# integrator_inverter.net
KiCad netlist of a schematic drawn in Altium Designer
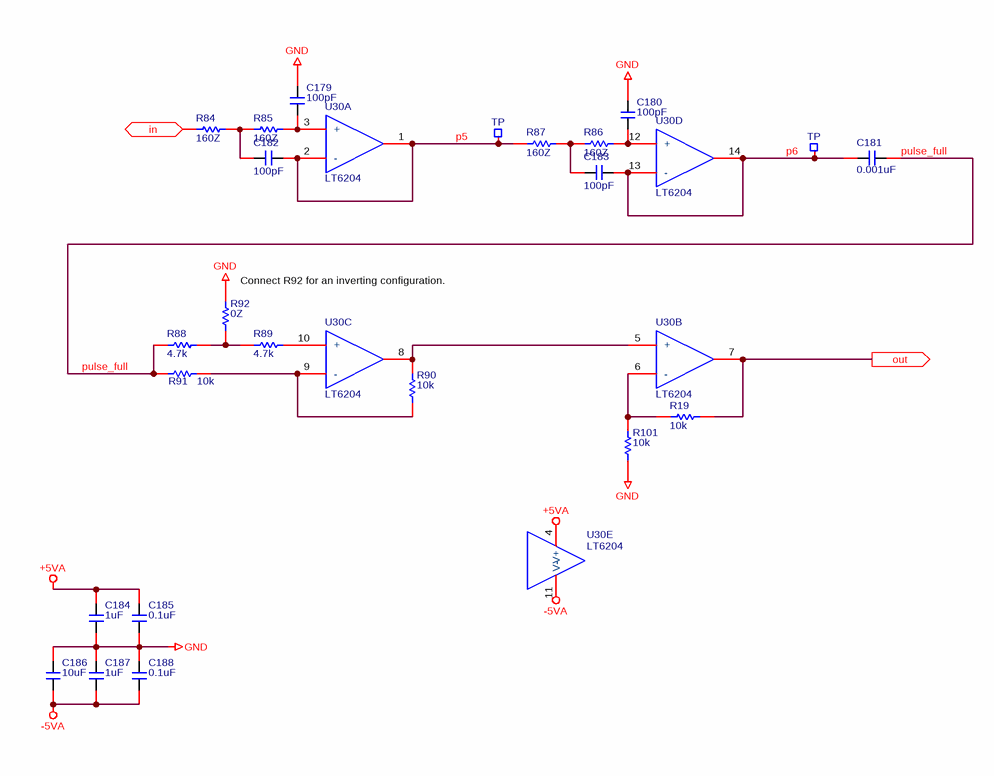
[diagram p0: integrator_inverter.SchDoc]

(export (version "E")
  (design (tool "Eeschema 10.0.6"))
  (components
    (comp (ref "C179")
      (value "100pF")
      (footprint "C0603")
      (description "CAP-CER, 0, 100pF, 10%, 50V, 0603")
      (fields
        (field (name "MANUFACTURER") "AVX Corporation")
        (field (name "MANUFACTURER PART NUMBER") "06035A101KAT2A")
      )
      (libsource (lib "stdlib") (part "AVX/06035A101KAT2A"))
    )
    (comp (ref "C180")
      (value "100pF")
      (footprint "C0603")
      (description "CAP-CER, 0, 100pF, 10%, 50V, 0603")
      (fields
        (field (name "MANUFACTURER") "AVX Corporation")
        (field (name "MANUFACTURER PART NUMBER") "06035A101KAT2A")
      )
      (libsource (lib "stdlib") (part "AVX/06035A101KAT2A"))
    )
    (comp (ref "C181")
      (value "0.001uF")
      (footprint "C0603")
      (description "CAP-CER, 0, 1000pF, 10%, 50V, 0603")
      (fields
        (field (name "MANUFACTURER") "Murata Electronics North America")
        (field (name "MANUFACTURER PART NUMBER") "GRM188R71H102KA01D")
      )
      (libsource (lib "stdlib") (part "CAP/GRM188R71H102KA01D"))
    )
    (comp (ref "C182")
      (value "100pF")
      (footprint "C0603")
      (description "CAP-CER, 0, 100pF, 10%, 50V, 0603")
      (fields
        (field (name "MANUFACTURER") "AVX Corporation")
        (field (name "MANUFACTURER PART NUMBER") "06035A101KAT2A")
      )
      (libsource (lib "stdlib") (part "AVX/06035A101KAT2A"))
    )
    (comp (ref "C183")
      (value "100pF")
      (footprint "C0603")
      (description "CAP-CER, 0, 100pF, 10%, 50V, 0603")
      (fields
        (field (name "MANUFACTURER") "AVX Corporation")
        (field (name "MANUFACTURER PART NUMBER") "06035A101KAT2A")
      )
      (libsource (lib "stdlib") (part "AVX/06035A101KAT2A"))
    )
    (comp (ref "C184")
      (value "1uF")
      (footprint "C0603")
      (description "CAP-CER, 2, 1.0uF, 10%, 25V, 0603")
      (fields
        (field (name "MANUFACTURER") "Murata Electronics North America")
        (field (name "MANUFACTURER PART NUMBER") "GRM188R61E105KA12D")
      )
      (libsource (lib "stdlib") (part "Murata/GRM188R61E105KA12D"))
    )
    (comp (ref "C185")
      (value "0.1uF")
      (footprint "C0603")
      (description "CAP-CER, 2, 0.1uF, 10%, 50V, 0603, X7R")
      (fields
        (field (name "MANUFACTURER") "AVX Corporation")
        (field (name "MANUFACTURER PART NUMBER") "06035C104KAT2A")
      )
      (libsource (lib "stdlib") (part "CAP/06035C104KAT2A"))
    )
    (comp (ref "C186")
      (value "10uF")
      (footprint "c1206")
      (description "CAP-CER, 2, 10uF, 10%, 35V, 1206")
      (fields
        (field (name "MANUFACTURER") "Taiyo Yuden")
        (field (name "MANUFACTURER PART NUMBER") "GMK316F106ZL-T")
      )
      (libsource (lib "stdlib") (part "CAP/GMK316F106ZL-T"))
    )
    (comp (ref "C187")
      (value "1uF")
      (footprint "C0603")
      (description "CAP-CER, 2, 1.0uF, 10%, 25V, 0603")
      (fields
        (field (name "MANUFACTURER") "Murata Electronics North America")
        (field (name "MANUFACTURER PART NUMBER") "GRM188R61E105KA12D")
      )
      (libsource (lib "stdlib") (part "Murata/GRM188R61E105KA12D"))
    )
    (comp (ref "C188")
      (value "0.1uF")
      (footprint "C0603")
      (description "CAP-CER, 2, 0.1uF, 10%, 50V, 0603, X7R")
      (fields
        (field (name "MANUFACTURER") "AVX Corporation")
        (field (name "MANUFACTURER PART NUMBER") "06035C104KAT2A")
      )
      (libsource (lib "stdlib") (part "CAP/06035C104KAT2A"))
    )
    (comp (ref "R19")
      (value "10k")
      (footprint "R0603")
      (description "RES1, SMD, 10.0k, 1.0%, 1/10W, 0603")
      (fields
        (field (name "MANUFACTURER") "Vishay Dale")
        (field (name "MANUFACTURER PART NUMBER") "CRCW060310K0FKEA")
      )
      (libsource (lib "stdlib") (part "CRCW060310K0FKEA"))
    )
    (comp (ref "R84")
      (value "160Z")
      (footprint "R0603")
      (description "RES0, SMD,  160Z, 1.0%, 1/10W, 0603")
      (fields
        (field (name "MANUFACTURER") "Vishay Dale")
        (field (name "MANUFACTURER PART NUMBER") "CRCW0603160RFKEA")
      )
      (libsource (lib "stdlib") (part "CRCW0603160RFKEA"))
    )
    (comp (ref "R85")
      (value "160Z")
      (footprint "R0603")
      (description "RES0, SMD,  160Z, 1.0%, 1/10W, 0603")
      (fields
        (field (name "MANUFACTURER") "Vishay Dale")
        (field (name "MANUFACTURER PART NUMBER") "CRCW0603160RFKEA")
      )
      (libsource (lib "stdlib") (part "CRCW0603160RFKEA"))
    )
    (comp (ref "R86")
      (value "160Z")
      (footprint "R0603")
      (description "RES0, SMD,  160Z, 1.0%, 1/10W, 0603")
      (fields
        (field (name "MANUFACTURER") "Vishay Dale")
        (field (name "MANUFACTURER PART NUMBER") "CRCW0603160RFKEA")
      )
      (libsource (lib "stdlib") (part "CRCW0603160RFKEA"))
    )
    (comp (ref "R87")
      (value "160Z")
      (footprint "R0603")
      (description "RES0, SMD,  160Z, 1.0%, 1/10W, 0603")
      (fields
        (field (name "MANUFACTURER") "Vishay Dale")
        (field (name "MANUFACTURER PART NUMBER") "CRCW0603160RFKEA")
      )
      (libsource (lib "stdlib") (part "CRCW0603160RFKEA"))
    )
    (comp (ref "R88")
      (value "4.7k")
      (footprint "R0603")
      (description "RES1, SMD, 4.70k, 1.0%, 1/10W, 0603")
      (fields
        (field (name "MANUFACTURER") "Vishay Dale")
        (field (name "MANUFACTURER PART NUMBER") "CRCW06034K70FKEA")
      )
      (libsource (lib "stdlib") (part "CRCW06034K70FKEA"))
    )
    (comp (ref "R89")
      (value "4.7k")
      (footprint "R0603")
      (description "RES1, SMD, 4.70k, 1.0%, 1/10W, 0603")
      (fields
        (field (name "MANUFACTURER") "Vishay Dale")
        (field (name "MANUFACTURER PART NUMBER") "CRCW06034K70FKEA")
      )
      (libsource (lib "stdlib") (part "CRCW06034K70FKEA"))
    )
    (comp (ref "R90")
      (value "10k")
      (footprint "R0603")
      (description "RES1, SMD, 10.0k, 1.0%, 1/10W, 0603")
      (fields
        (field (name "MANUFACTURER") "Vishay Dale")
        (field (name "MANUFACTURER PART NUMBER") "CRCW060310K0FKEA")
      )
      (libsource (lib "stdlib") (part "CRCW060310K0FKEA"))
    )
    (comp (ref "R91")
      (value "10k")
      (footprint "R0603")
      (description "RES1, SMD, 10.0k, 1.0%, 1/10W, 0603")
      (fields
        (field (name "MANUFACTURER") "Vishay Dale")
        (field (name "MANUFACTURER PART NUMBER") "CRCW060310K0FKEA")
      )
      (libsource (lib "stdlib") (part "CRCW060310K0FKEA"))
    )
    (comp (ref "R92")
      (value "0Z")
      (footprint "R0603")
      (description "RES0, SMD, 0.00Z, 0603")
      (fields
        (field (name "MANUFACTURER") "Vishay Dale")
        (field (name "MANUFACTURER PART NUMBER") "CRCW06030000Z0EA")
      )
      (libsource (lib "stdlib") (part "CRCW06030000Z0EA"))
    )
    (comp (ref "R101")
      (value "10k")
      (footprint "R0603")
      (description "RES1, SMD, 10.0k, 1.0%, 1/10W, 0603")
      (fields
        (field (name "MANUFACTURER") "Vishay Dale")
        (field (name "MANUFACTURER PART NUMBER") "CRCW060310K0FKEA")
      )
      (libsource (lib "stdlib") (part "CRCW060310K0FKEA"))
    )
    (comp (ref "TP36")
      (value "TP")
      (footprint "TP_MICRO")
      (description "Test Point, Round, Small")
      (libsource (lib "stdlib") (part "TP_MICRO"))
    )
    (comp (ref "TP37")
      (value "TP")
      (footprint "TP_MICRO")
      (description "Test Point, Round, Small")
      (libsource (lib "stdlib") (part "TP_MICRO"))
    )
    (comp (ref "U30")
      (value "LT6204")
      (footprint "SOIC-14")
      (description "OPA, 100MHz, Quad, RRIO, Unity Stable")
      (libsource (lib "stdlib") (part "LT6204 SOIC-14"))
    )
  )
  (nets
    (net (code "1") (name "+5VA") (class "Default")
      (node (ref "C184") (pin "2") (pinfunction "2_2") (pintype "passive"))
      (node (ref "C185") (pin "2") (pinfunction "2_2") (pintype "passive"))
      (node (ref "U30") (pin "4") (pinfunction "V+_4") (pintype "passive"))
    )
    (net (code "2") (name "-5VA") (class "Default")
      (node (ref "C186") (pin "1") (pinfunction "5_1") (pintype "passive"))
      (node (ref "C187") (pin "1") (pinfunction "5_1") (pintype "passive"))
      (node (ref "C188") (pin "1") (pinfunction "5_1") (pintype "passive"))
      (node (ref "U30") (pin "11") (pinfunction "V-_11") (pintype "passive"))
    )
    (net (code "3") (name "/in") (class "Default")
      (node (ref "R84") (pin "1") (pinfunction "1_1") (pintype "passive"))
    )
    (net (code "4") (name "/out") (class "Default")
      (node (ref "R19") (pin "2") (pinfunction "2_2") (pintype "passive"))
      (node (ref "U30") (pin "7") (pinfunction "OUT_7") (pintype "passive"))
    )
    (net (code "5") (name "/p5") (class "Default")
      (node (ref "C182") (pin "2") (pinfunction "2_2") (pintype "passive"))
      (node (ref "R87") (pin "1") (pinfunction "1_1") (pintype "passive"))
      (node (ref "TP36") (pin "1") (pinfunction "1_1") (pintype "passive"))
      (node (ref "U30") (pin "1") (pinfunction "OUT_1") (pintype "passive"))
      (node (ref "U30") (pin "2") (pinfunction "-_2") (pintype "passive"))
    )
    (net (code "6") (name "/p6") (class "Default")
      (node (ref "C181") (pin "2") (pinfunction "2_2") (pintype "passive"))
      (node (ref "C183") (pin "2") (pinfunction "2_2") (pintype "passive"))
      (node (ref "TP37") (pin "1") (pinfunction "1_1") (pintype "passive"))
      (node (ref "U30") (pin "13") (pinfunction "-_13") (pintype "passive"))
      (node (ref "U30") (pin "14") (pinfunction "OUT_14") (pintype "passive"))
    )
    (net (code "7") (name "/pulse_full") (class "Default")
      (node (ref "C181") (pin "1") (pinfunction "1_1") (pintype "passive"))
      (node (ref "R88") (pin "1") (pinfunction "1_1") (pintype "passive"))
      (node (ref "R91") (pin "1") (pinfunction "1_1") (pintype "passive"))
    )
    (net (code "8") (name "GND") (class "Default")
      (node (ref "C179") (pin "2") (pinfunction "2_2") (pintype "passive"))
      (node (ref "C180") (pin "2") (pinfunction "2_2") (pintype "passive"))
      (node (ref "C184") (pin "1") (pinfunction "5_1") (pintype "passive"))
      (node (ref "C185") (pin "1") (pinfunction "5_1") (pintype "passive"))
      (node (ref "C186") (pin "2") (pinfunction "2_2") (pintype "passive"))
      (node (ref "C187") (pin "2") (pinfunction "2_2") (pintype "passive"))
      (node (ref "C188") (pin "2") (pinfunction "2_2") (pintype "passive"))
      (node (ref "R101") (pin "2") (pinfunction "2_2") (pintype "passive"))
      (node (ref "R92") (pin "1") (pinfunction "1_1") (pintype "passive"))
    )
    (net (code "9") (name "Net-(C179-5)") (class "Default")
      (node (ref "C179") (pin "1") (pinfunction "5_1") (pintype "passive"))
      (node (ref "R85") (pin "2") (pinfunction "2_2") (pintype "passive"))
      (node (ref "U30") (pin "3") (pinfunction "+_3") (pintype "passive"))
    )
    (net (code "10") (name "Net-(C180-5)") (class "Default")
      (node (ref "C180") (pin "1") (pinfunction "5_1") (pintype "passive"))
      (node (ref "R86") (pin "2") (pinfunction "2_2") (pintype "passive"))
      (node (ref "U30") (pin "12") (pinfunction "+_12") (pintype "passive"))
    )
    (net (code "11") (name "Net-(C182-5)") (class "Default")
      (node (ref "C182") (pin "1") (pinfunction "5_1") (pintype "passive"))
      (node (ref "R84") (pin "2") (pinfunction "2_2") (pintype "passive"))
      (node (ref "R85") (pin "1") (pinfunction "1_1") (pintype "passive"))
    )
    (net (code "12") (name "Net-(C183-5)") (class "Default")
      (node (ref "C183") (pin "1") (pinfunction "5_1") (pintype "passive"))
      (node (ref "R86") (pin "1") (pinfunction "1_1") (pintype "passive"))
      (node (ref "R87") (pin "2") (pinfunction "2_2") (pintype "passive"))
    )
    (net (code "13") (name "Net-(R88-Pad2)") (class "Default")
      (node (ref "R88") (pin "2") (pinfunction "2_2") (pintype "passive"))
      (node (ref "R89") (pin "1") (pinfunction "1_1") (pintype "passive"))
      (node (ref "R92") (pin "2") (pinfunction "2_2") (pintype "passive"))
    )
    (net (code "14") (name "Net-(U30B-+)") (class "Default")
      (node (ref "R90") (pin "1") (pinfunction "1_1") (pintype "passive"))
      (node (ref "U30") (pin "5") (pinfunction "+_5") (pintype "passive"))
      (node (ref "U30") (pin "8") (pinfunction "OUT_8") (pintype "passive"))
    )
    (net (code "15") (name "Net-(U30B--)") (class "Default")
      (node (ref "R101") (pin "1") (pinfunction "1_1") (pintype "passive"))
      (node (ref "R19") (pin "1") (pinfunction "1_1") (pintype "passive"))
      (node (ref "U30") (pin "6") (pinfunction "-_6") (pintype "passive"))
    )
    (net (code "16") (name "Net-(U30C-+)") (class "Default")
      (node (ref "R89") (pin "2") (pinfunction "2_2") (pintype "passive"))
      (node (ref "U30") (pin "10") (pinfunction "+_10") (pintype "passive"))
    )
    (net (code "17") (name "Net-(U30C--)") (class "Default")
      (node (ref "R90") (pin "2") (pinfunction "2_2") (pintype "passive"))
      (node (ref "R91") (pin "2") (pinfunction "2_2") (pintype "passive"))
      (node (ref "U30") (pin "9") (pinfunction "-_9") (pintype "passive"))
    )
  )
)
